# L298.net
KiCad netlist of a schematic drawn in Altium Designer
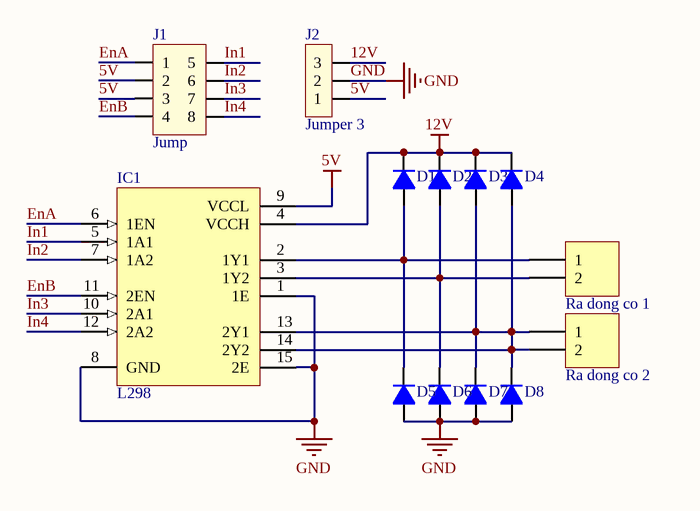
[diagram p0: L298.SchDoc]

(export (version "E")
  (design (tool "Eeschema 10.0.6"))
  (components
    (comp (ref "D1")
      (value "~")
      (footprint "D1A")
      (description "Diode 1A")
      (libsource (lib "syhaunguyen") (part "D1A"))
    )
    (comp (ref "D2")
      (value "~")
      (footprint "D1A")
      (description "Diode 1A")
      (libsource (lib "syhaunguyen") (part "D1A"))
    )
    (comp (ref "D3")
      (value "~")
      (footprint "D1A")
      (description "Diode 1A")
      (libsource (lib "syhaunguyen") (part "D1A"))
    )
    (comp (ref "D4")
      (value "~")
      (footprint "D1A")
      (description "Diode 1A")
      (libsource (lib "syhaunguyen") (part "D1A"))
    )
    (comp (ref "D5")
      (value "~")
      (footprint "D1A")
      (description "Diode 1A")
      (libsource (lib "syhaunguyen") (part "D1A"))
    )
    (comp (ref "D6")
      (value "~")
      (footprint "D1A")
      (description "Diode 1A")
      (libsource (lib "syhaunguyen") (part "D1A"))
    )
    (comp (ref "D7")
      (value "~")
      (footprint "D1A")
      (description "Diode 1A")
      (libsource (lib "syhaunguyen") (part "D1A"))
    )
    (comp (ref "D8")
      (value "~")
      (footprint "D1A")
      (description "Diode 1A")
      (libsource (lib "syhaunguyen") (part "D1A"))
    )
    (comp (ref "IC1")
      (value "L298")
      (footprint "DIP15SL2")
      (description "Dual Full-H Driver")
      (fields (field (name "PUBLISHER") "Altium Limited"))
      (libsource (lib "syhaunguyen") (part "L298"))
    )
    (comp (ref "J1")
      (value "Jump")
      (footprint "JP4x2")
      (description "Connector 4x2")
      (libsource (lib "syhaunguyen") (part "JP4x2"))
    )
    (comp (ref "J2") (value "Jumper 3") (footprint "JP3") (libsource (lib "syhaunguyen") (part "JP3")))
    (comp (ref "Ra dong co 1")
      (value "Header 2")
      (footprint "JP2")
      (description "Header, 2-Pin")
      (fields (field (name "PUBLISHER") "Altium Limited"))
      (libsource (lib "TechMT.VN_Lib_Project v1.0") (part "Header 2"))
    )
    (comp (ref "Ra dong co 2")
      (value "Header 2")
      (footprint "JP2")
      (description "Header, 2-Pin")
      (fields (field (name "PUBLISHER") "Altium Limited"))
      (libsource (lib "TechMT.VN_Lib_Project v1.0") (part "Header 2"))
    )
  )
  (nets
    (net (code "1") (name "/EnA") (class "Default")
      (node (ref "IC1") (pin "6") (pinfunction "1EN_6") (pintype "input"))
      (node (ref "J1") (pin "1") (pinfunction "1_1") (pintype "passive"))
    )
    (net (code "2") (name "/EnB") (class "Default")
      (node (ref "IC1") (pin "11") (pinfunction "2EN_11") (pintype "input"))
      (node (ref "J1") (pin "4") (pinfunction "4_4") (pintype "passive"))
    )
    (net (code "3") (name "/In1") (class "Default")
      (node (ref "IC1") (pin "5") (pinfunction "1A1_5") (pintype "input"))
      (node (ref "J1") (pin "5") (pinfunction "5_5") (pintype "passive"))
    )
    (net (code "4") (name "/In2") (class "Default")
      (node (ref "IC1") (pin "7") (pinfunction "1A2_7") (pintype "input"))
      (node (ref "J1") (pin "6") (pinfunction "6_6") (pintype "passive"))
    )
    (net (code "5") (name "/In3") (class "Default")
      (node (ref "IC1") (pin "10") (pinfunction "2A1_10") (pintype "input"))
      (node (ref "J1") (pin "7") (pinfunction "7_7") (pintype "passive"))
    )
    (net (code "6") (name "/In4") (class "Default")
      (node (ref "IC1") (pin "12") (pinfunction "2A2_12") (pintype "input"))
      (node (ref "J1") (pin "8") (pinfunction "8_8") (pintype "passive"))
    )
    (net (code "7") (name "5V") (class "Default")
      (node (ref "IC1") (pin "9") (pinfunction "VCCL_9") (pintype "power_in"))
      (node (ref "J1") (pin "2") (pinfunction "2_2") (pintype "passive"))
      (node (ref "J1") (pin "3") (pinfunction "3_3") (pintype "passive"))
      (node (ref "J2") (pin "1") (pinfunction "1_1") (pintype "passive"))
    )
    (net (code "8") (name "12V") (class "Default")
      (node (ref "D1") (pin "2") (pinfunction "K_2") (pintype "passive"))
      (node (ref "D2") (pin "2") (pinfunction "K_2") (pintype "passive"))
      (node (ref "D3") (pin "2") (pinfunction "K_2") (pintype "passive"))
      (node (ref "D4") (pin "2") (pinfunction "K_2") (pintype "passive"))
      (node (ref "IC1") (pin "4") (pinfunction "VCCH_4") (pintype "power_in"))
      (node (ref "J2") (pin "3") (pinfunction "3_3") (pintype "passive"))
    )
    (net (code "9") (name "GND") (class "Default")
      (node (ref "D5") (pin "1") (pinfunction "A_1") (pintype "passive"))
      (node (ref "D6") (pin "1") (pinfunction "A_1") (pintype "passive"))
      (node (ref "D7") (pin "1") (pinfunction "A_1") (pintype "passive"))
      (node (ref "D8") (pin "1") (pinfunction "A_1") (pintype "passive"))
      (node (ref "IC1") (pin "1") (pinfunction "1E_1") (pintype "passive"))
      (node (ref "IC1") (pin "15") (pinfunction "2E_15") (pintype "passive"))
      (node (ref "IC1") (pin "8") (pinfunction "GND_8") (pintype "power_in"))
      (node (ref "J2") (pin "2") (pinfunction "2_2") (pintype "passive"))
    )
    (net (code "10") (name "Net-(D1-A)") (class "Default")
      (node (ref "D1") (pin "1") (pinfunction "A_1") (pintype "passive"))
      (node (ref "D5") (pin "2") (pinfunction "K_2") (pintype "passive"))
      (node (ref "IC1") (pin "2") (pinfunction "1Y1_2") (pintype "tri_state"))
      (node (ref "Ra dong co 1") (pin "1") (pinfunction "1_1") (pintype "passive"))
    )
    (net (code "11") (name "Net-(D2-A)") (class "Default")
      (node (ref "D2") (pin "1") (pinfunction "A_1") (pintype "passive"))
      (node (ref "D6") (pin "2") (pinfunction "K_2") (pintype "passive"))
      (node (ref "IC1") (pin "3") (pinfunction "1Y2_3") (pintype "tri_state"))
      (node (ref "Ra dong co 1") (pin "2") (pinfunction "2_2") (pintype "passive"))
    )
    (net (code "12") (name "Net-(D3-A)") (class "Default")
      (node (ref "D3") (pin "1") (pinfunction "A_1") (pintype "passive"))
      (node (ref "D4") (pin "1") (pinfunction "A_1") (pintype "passive"))
      (node (ref "D7") (pin "2") (pinfunction "K_2") (pintype "passive"))
      (node (ref "D8") (pin "2") (pinfunction "K_2") (pintype "passive"))
      (node (ref "IC1") (pin "13") (pinfunction "2Y1_13") (pintype "tri_state"))
      (node (ref "IC1") (pin "14") (pinfunction "2Y2_14") (pintype "tri_state"))
      (node (ref "Ra dong co 2") (pin "1") (pinfunction "1_1") (pintype "passive"))
      (node (ref "Ra dong co 2") (pin "2") (pinfunction "2_2") (pintype "passive"))
    )
  )
)
